# MercurialSDR_MISC.net
KiCad netlist of a schematic drawn in Altium Designer
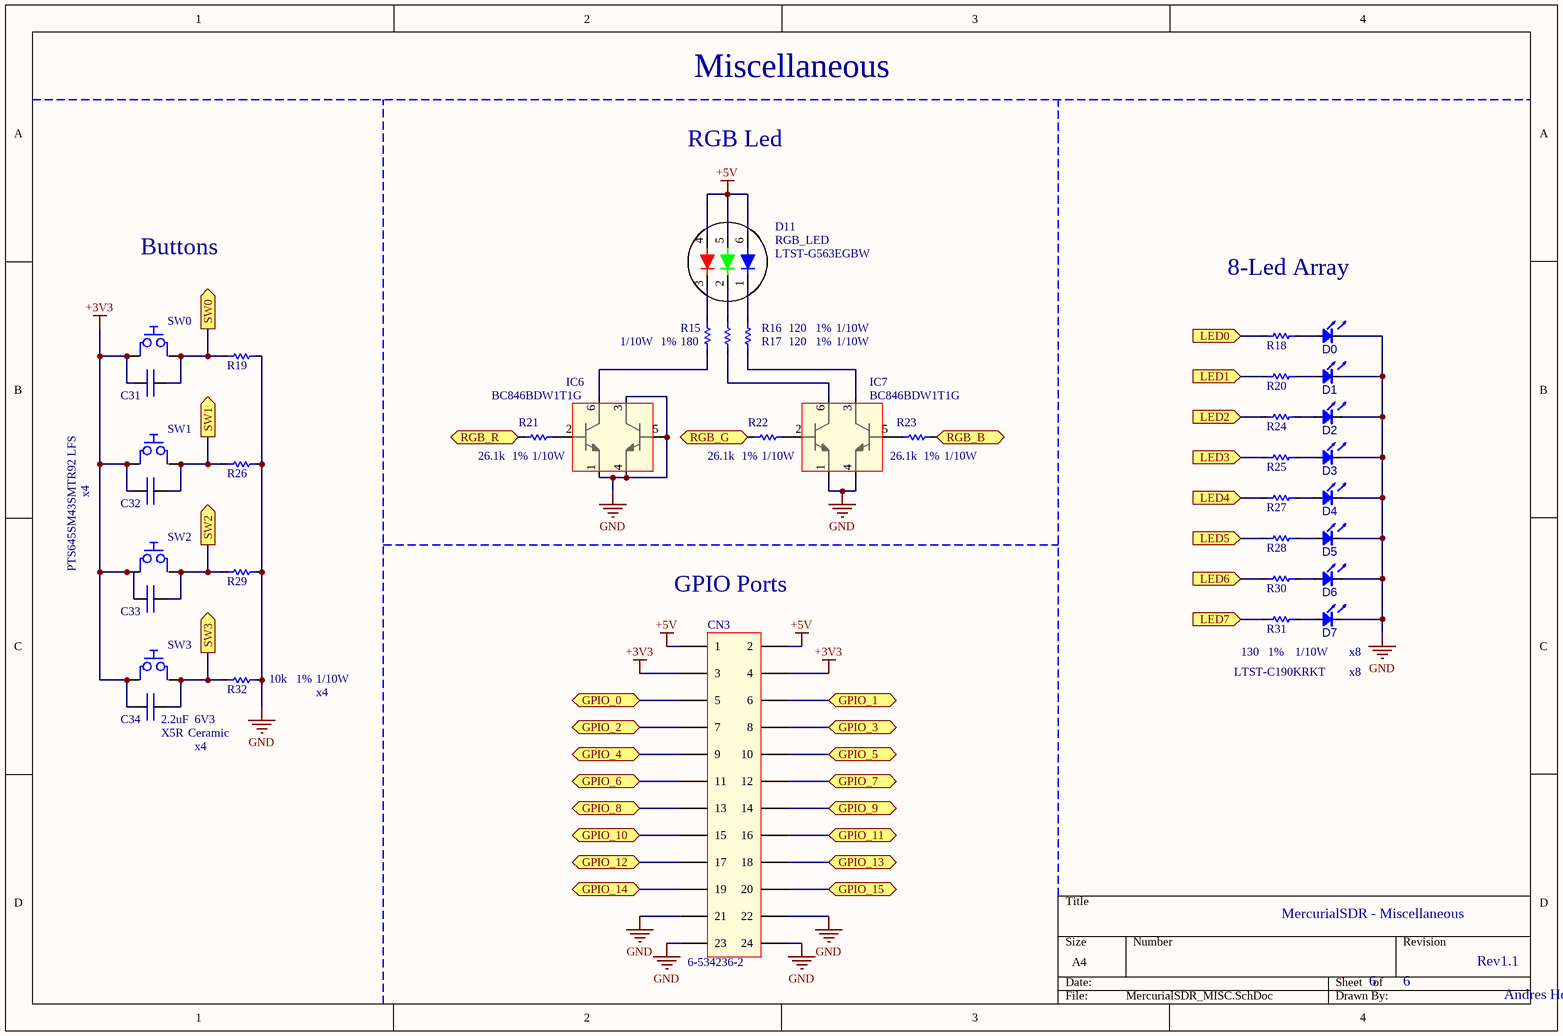
[diagram p0: MercurialSDR_MISC.SchDoc]

(export (version "E")
  (design (tool "Eeschema 10.0.6"))
  (components
    (comp (ref "C31")
      (value "Capacitor")
      (footprint "CAP_0603")
      (description "Capacitor no polarizado")
      (fields (field (name "PART NUMBER") "CL10A225KQ8NNNC"))
      (libsource (lib "MercurialSDR") (part "Cap"))
    )
    (comp (ref "C32")
      (value "Capacitor")
      (footprint "CAP_0603")
      (description "Capacitor no polarizado")
      (fields (field (name "PART NUMBER") "CL10A225KQ8NNNC"))
      (libsource (lib "MercurialSDR") (part "Cap"))
    )
    (comp (ref "C33")
      (value "Capacitor")
      (footprint "CAP_0603")
      (description "Capacitor no polarizado")
      (fields (field (name "PART NUMBER") "CL10A225KQ8NNNC"))
      (libsource (lib "MercurialSDR") (part "Cap"))
    )
    (comp (ref "C34")
      (value "2.2uF")
      (footprint "CAP_0603")
      (description "Capacitor no polarizado")
      (fields
        (field (name "TEMP COEF") "X5R")
        (field (name "PART NUMBER") "CL10A225KQ8NNNC")
        (field (name "VR") "6V3")
        (field (name "MATERIAL") "Ceramic")
        (field (name "Comment") "Capacitor")
      )
      (libsource (lib "MercurialSDR") (part "Cap"))
    )
    (comp (ref "CN3")
      (value "Connector")
      (footprint "CON_12x2")
      (description "Conector genérico 12x2")
      (fields (field (name "PART NUMBER") "6-534236-2"))
      (libsource (lib "MercurialSDR") (part "CN_12x2"))
    )
    (comp (ref "D0")
      (value "Led_small")
      (footprint "LED_0603")
      (fields (field (name "PART NUMBER") "LTST-C190KRKT"))
      (libsource (lib "MercurialSDR") (part "Led_small"))
    )
    (comp (ref "D1")
      (value "Led_small")
      (footprint "LED_0603")
      (fields (field (name "PART NUMBER") "LTST-C190KRKT"))
      (libsource (lib "MercurialSDR") (part "Led_small"))
    )
    (comp (ref "D2")
      (value "Led_small")
      (footprint "LED_0603")
      (fields (field (name "PART NUMBER") "LTST-C190KRKT"))
      (libsource (lib "MercurialSDR") (part "Led_small"))
    )
    (comp (ref "D3")
      (value "Led_small")
      (footprint "LED_0603")
      (fields (field (name "PART NUMBER") "LTST-C190KRKT"))
      (libsource (lib "MercurialSDR") (part "Led_small"))
    )
    (comp (ref "D4")
      (value "Led_small")
      (footprint "LED_0603")
      (fields (field (name "PART NUMBER") "LTST-C190KRKT"))
      (libsource (lib "MercurialSDR") (part "Led_small"))
    )
    (comp (ref "D5")
      (value "Led_small")
      (footprint "LED_0603")
      (fields (field (name "PART NUMBER") "LTST-C190KRKT"))
      (libsource (lib "MercurialSDR") (part "Led_small"))
    )
    (comp (ref "D6")
      (value "Led_small")
      (footprint "LED_0603")
      (fields (field (name "PART NUMBER") "LTST-C190KRKT"))
      (libsource (lib "MercurialSDR") (part "Led_small"))
    )
    (comp (ref "D7")
      (value "Led_small")
      (footprint "LED_0603")
      (fields (field (name "PART NUMBER") "LTST-C190KRKT"))
      (libsource (lib "MercurialSDR") (part "Led_small"))
    )
    (comp (ref "D11")
      (value "RGB_LED")
      (footprint "LED_RGB 5x5mm")
      (description "Led RGB")
      (fields (field (name "PART NUMBER") "LTST-G563EGBW"))
      (libsource (lib "MercurialSDR") (part "LED_RGB"))
    )
    (comp (ref "IC6")
      (value "BC846")
      (footprint "TSSOP-6")
      (description "TBJ NPN Dual")
      (fields (field (name "PART NUMBER") "BC846BDW1T1G"))
      (libsource (lib "MercurialSDR") (part "BC846BDW_1"))
    )
    (comp (ref "IC7")
      (value "BC846")
      (footprint "TSSOP-6")
      (description "TBJ NPN Dual")
      (fields (field (name "PART NUMBER") "BC846BDW1T1G"))
      (libsource (lib "MercurialSDR") (part "BC846BDW_1"))
    )
    (comp (ref "R15")
      (value "180")
      (footprint "RES_0603")
      (description "Resistor")
      (fields
        (field (name "POWER") "1/10W")
        (field (name "PART NUMBER") "CR0603-FX-1800ELF")
        (field (name "TOLERANCE") "1%")
        (field (name "Comment") "Resistor SMD")
      )
      (libsource (lib "MercurialSDR") (part "Res"))
    )
    (comp (ref "R16")
      (value "120")
      (footprint "RES_0603")
      (description "Resistor")
      (fields
        (field (name "POWER") "1/10W")
        (field (name "PART NUMBER") "CR0603-FX-1200ELF")
        (field (name "TOLERANCE") "1%")
        (field (name "Comment") "Resistor SMD")
      )
      (libsource (lib "MercurialSDR") (part "Res"))
    )
    (comp (ref "R17")
      (value "120")
      (footprint "RES_0603")
      (description "Resistor")
      (fields
        (field (name "POWER") "1/10W")
        (field (name "PART NUMBER") "CR0603-FX-1200ELF")
        (field (name "TOLERANCE") "1%")
        (field (name "Comment") "Resistor SMD")
      )
      (libsource (lib "MercurialSDR") (part "Res"))
    )
    (comp (ref "R18")
      (value "Resistor SMD")
      (footprint "RES_0603")
      (description "Resistor")
      (fields (field (name "POWER") "1/10W") (field (name "PART NUMBER") "CR0603-FX-1300ELF"))
      (libsource (lib "MercurialSDR") (part "Res"))
    )
    (comp (ref "R19")
      (value "10k")
      (footprint "RES_0603")
      (description "Resistor")
      (fields
        (field (name "POWER") "1/10W")
        (field (name "PART NUMBER") "CR0603-FX-1002EAS")
        (field (name "TOLERANCE") "1%")
        (field (name "Comment") "Resistor SMD")
      )
      (libsource (lib "MercurialSDR") (part "Res"))
    )
    (comp (ref "R20")
      (value "Resistor SMD")
      (footprint "RES_0603")
      (description "Resistor")
      (fields (field (name "POWER") "1/10W") (field (name "PART NUMBER") "CR0603-FX-1300ELF"))
      (libsource (lib "MercurialSDR") (part "Res"))
    )
    (comp (ref "R21")
      (value "26.1k")
      (footprint "RES_0603")
      (description "Resistor")
      (fields
        (field (name "POWER") "1/10W")
        (field (name "PART NUMBER") "CR0603-FX-2612ELF")
        (field (name "TOLERANCE") "1%")
        (field (name "Comment") "Resistor SMD")
      )
      (libsource (lib "MercurialSDR") (part "Res"))
    )
    (comp (ref "R22")
      (value "26.1k")
      (footprint "RES_0603")
      (description "Resistor")
      (fields
        (field (name "POWER") "1/10W")
        (field (name "PART NUMBER") "CR0603-FX-2612ELF")
        (field (name "TOLERANCE") "1%")
        (field (name "Comment") "Resistor SMD")
      )
      (libsource (lib "MercurialSDR") (part "Res"))
    )
    (comp (ref "R23")
      (value "26.1k")
      (footprint "RES_0603")
      (description "Resistor")
      (fields
        (field (name "POWER") "1/10W")
        (field (name "PART NUMBER") "CR0603-FX-2612ELF")
        (field (name "TOLERANCE") "1%")
        (field (name "Comment") "Resistor SMD")
      )
      (libsource (lib "MercurialSDR") (part "Res"))
    )
    (comp (ref "R24")
      (value "Resistor SMD")
      (footprint "RES_0603")
      (description "Resistor")
      (fields (field (name "POWER") "1/10W") (field (name "PART NUMBER") "CR0603-FX-1300ELF"))
      (libsource (lib "MercurialSDR") (part "Res"))
    )
    (comp (ref "R25")
      (value "Resistor SMD")
      (footprint "RES_0603")
      (description "Resistor")
      (fields (field (name "POWER") "1/10W") (field (name "PART NUMBER") "CR0603-FX-1300ELF"))
      (libsource (lib "MercurialSDR") (part "Res"))
    )
    (comp (ref "R26")
      (value "Resistor SMD")
      (footprint "RES_0603")
      (description "Resistor")
      (fields (field (name "POWER") "1/10W") (field (name "PART NUMBER") "CR0603-FX-1002EAS"))
      (libsource (lib "MercurialSDR") (part "Res"))
    )
    (comp (ref "R27")
      (value "Resistor SMD")
      (footprint "RES_0603")
      (description "Resistor")
      (fields (field (name "POWER") "1/10W") (field (name "PART NUMBER") "CR0603-FX-1300ELF"))
      (libsource (lib "MercurialSDR") (part "Res"))
    )
    (comp (ref "R28")
      (value "Resistor SMD")
      (footprint "RES_0603")
      (description "Resistor")
      (fields (field (name "POWER") "1/10W") (field (name "PART NUMBER") "CR0603-FX-1300ELF"))
      (libsource (lib "MercurialSDR") (part "Res"))
    )
    (comp (ref "R29")
      (value "Resistor SMD")
      (footprint "RES_0603")
      (description "Resistor")
      (fields (field (name "POWER") "1/10W") (field (name "PART NUMBER") "CR0603-FX-1002EAS"))
      (libsource (lib "MercurialSDR") (part "Res"))
    )
    (comp (ref "R30")
      (value "Resistor SMD")
      (footprint "RES_0603")
      (description "Resistor")
      (fields (field (name "POWER") "1/10W") (field (name "PART NUMBER") "CR0603-FX-1300ELF"))
      (libsource (lib "MercurialSDR") (part "Res"))
    )
    (comp (ref "R31")
      (value "130")
      (footprint "RES_0603")
      (description "Resistor")
      (fields
        (field (name "POWER") "1/10W")
        (field (name "PART NUMBER") "CR0603-FX-1300ELF")
        (field (name "TOLERANCE") "1%")
        (field (name "Comment") "Resistor SMD")
      )
      (libsource (lib "MercurialSDR") (part "Res"))
    )
    (comp (ref "R32")
      (value "Resistor SMD")
      (footprint "RES_0603")
      (description "Resistor")
      (fields (field (name "POWER") "1/10W") (field (name "PART NUMBER") "CR0603-FX-1002EAS"))
      (libsource (lib "MercurialSDR") (part "Res"))
    )
    (comp (ref "SW0")
      (value "Pulsador")
      (footprint "SWITCH_6X6mm")
      (fields (field (name "PART NUMBER") "PTS645SM43SMTR92 LFS"))
      (libsource (lib "MercurialSDR") (part "Pulsador"))
    )
    (comp (ref "SW1")
      (value "Pulsador")
      (footprint "SWITCH_6X6mm")
      (fields (field (name "PART NUMBER") "PTS645SM43SMTR92 LFS"))
      (libsource (lib "MercurialSDR") (part "Pulsador"))
    )
    (comp (ref "SW2")
      (value "Pulsador")
      (footprint "SWITCH_6X6mm")
      (fields (field (name "PART NUMBER") "PTS645SM43SMTR92 LFS"))
      (libsource (lib "MercurialSDR") (part "Pulsador"))
    )
    (comp (ref "SW3")
      (value "Pulsador")
      (footprint "SWITCH_6X6mm")
      (fields (field (name "PART NUMBER") "PTS645SM43SMTR92 LFS"))
      (libsource (lib "MercurialSDR") (part "Pulsador"))
    )
  )
  (nets
    (net (code "1") (name "+3V3") (class "Default")
      (node (ref "C31") (pin "1") (pinfunction "1_1") (pintype "passive"))
      (node (ref "C32") (pin "1") (pinfunction "1_1") (pintype "passive"))
      (node (ref "C33") (pin "1") (pinfunction "1_1") (pintype "passive"))
      (node (ref "C34") (pin "1") (pinfunction "1_1") (pintype "passive"))
      (node (ref "CN3") (pin "3") (pinfunction "3_3") (pintype "passive"))
      (node (ref "CN3") (pin "4") (pinfunction "4_4") (pintype "passive"))
      (node (ref "SW0") (pin "1") (pinfunction "1_1") (pintype "passive"))
      (node (ref "SW1") (pin "1") (pinfunction "1_1") (pintype "passive"))
      (node (ref "SW2") (pin "1") (pinfunction "1_1") (pintype "passive"))
      (node (ref "SW3") (pin "1") (pinfunction "1_1") (pintype "passive"))
    )
    (net (code "2") (name "+5V") (class "Default")
      (node (ref "CN3") (pin "1") (pinfunction "1_1") (pintype "passive"))
      (node (ref "CN3") (pin "2") (pinfunction "2_2") (pintype "passive"))
      (node (ref "D11") (pin "4") (pinfunction "RA_4") (pintype "passive"))
      (node (ref "D11") (pin "5") (pinfunction "GA_5") (pintype "passive"))
      (node (ref "D11") (pin "6") (pinfunction "BA_6") (pintype "passive"))
    )
    (net (code "3") (name "/GPIO_0") (class "Default")
      (node (ref "CN3") (pin "5") (pinfunction "5_5") (pintype "passive"))
    )
    (net (code "4") (name "/GPIO_1") (class "Default")
      (node (ref "CN3") (pin "6") (pinfunction "6_6") (pintype "passive"))
    )
    (net (code "5") (name "/GPIO_2") (class "Default")
      (node (ref "CN3") (pin "7") (pinfunction "7_7") (pintype "passive"))
    )
    (net (code "6") (name "/GPIO_3") (class "Default")
      (node (ref "CN3") (pin "8") (pinfunction "8_8") (pintype "passive"))
    )
    (net (code "7") (name "/GPIO_4") (class "Default")
      (node (ref "CN3") (pin "9") (pinfunction "9_9") (pintype "passive"))
    )
    (net (code "8") (name "/GPIO_5") (class "Default")
      (node (ref "CN3") (pin "10") (pinfunction "10_10") (pintype "passive"))
    )
    (net (code "9") (name "/GPIO_6") (class "Default")
      (node (ref "CN3") (pin "11") (pinfunction "11_11") (pintype "passive"))
    )
    (net (code "10") (name "/GPIO_7") (class "Default")
      (node (ref "CN3") (pin "12") (pinfunction "12_12") (pintype "passive"))
    )
    (net (code "11") (name "/GPIO_8") (class "Default")
      (node (ref "CN3") (pin "13") (pinfunction "13_13") (pintype "passive"))
    )
    (net (code "12") (name "/GPIO_9") (class "Default")
      (node (ref "CN3") (pin "14") (pinfunction "14_14") (pintype "passive"))
    )
    (net (code "13") (name "/GPIO_10") (class "Default")
      (node (ref "CN3") (pin "15") (pinfunction "15_15") (pintype "passive"))
    )
    (net (code "14") (name "/GPIO_11") (class "Default")
      (node (ref "CN3") (pin "16") (pinfunction "16_16") (pintype "passive"))
    )
    (net (code "15") (name "/GPIO_12") (class "Default")
      (node (ref "CN3") (pin "17") (pinfunction "17_17") (pintype "passive"))
    )
    (net (code "16") (name "/GPIO_13") (class "Default")
      (node (ref "CN3") (pin "18") (pinfunction "18_18") (pintype "passive"))
    )
    (net (code "17") (name "/GPIO_14") (class "Default")
      (node (ref "CN3") (pin "19") (pinfunction "19_19") (pintype "passive"))
    )
    (net (code "18") (name "/GPIO_15") (class "Default")
      (node (ref "CN3") (pin "20") (pinfunction "20_20") (pintype "passive"))
    )
    (net (code "19") (name "/LED0") (class "Default")
      (node (ref "R18") (pin "2") (pinfunction "2_2") (pintype "passive"))
    )
    (net (code "20") (name "/LED1") (class "Default")
      (node (ref "R20") (pin "2") (pinfunction "2_2") (pintype "passive"))
    )
    (net (code "21") (name "/LED2") (class "Default")
      (node (ref "R24") (pin "2") (pinfunction "2_2") (pintype "passive"))
    )
    (net (code "22") (name "/LED3") (class "Default")
      (node (ref "R25") (pin "2") (pinfunction "2_2") (pintype "passive"))
    )
    (net (code "23") (name "/LED4") (class "Default")
      (node (ref "R27") (pin "2") (pinfunction "2_2") (pintype "passive"))
    )
    (net (code "24") (name "/LED5") (class "Default")
      (node (ref "R28") (pin "2") (pinfunction "2_2") (pintype "passive"))
    )
    (net (code "25") (name "/LED6") (class "Default")
      (node (ref "R30") (pin "2") (pinfunction "2_2") (pintype "passive"))
    )
    (net (code "26") (name "/LED7") (class "Default")
      (node (ref "R31") (pin "2") (pinfunction "2_2") (pintype "passive"))
    )
    (net (code "27") (name "/RGB_B") (class "Default")
      (node (ref "R23") (pin "1") (pinfunction "1_1") (pintype "passive"))
    )
    (net (code "28") (name "/RGB_G") (class "Default")
      (node (ref "R22") (pin "2") (pinfunction "2_2") (pintype "passive"))
    )
    (net (code "29") (name "/RGB_R") (class "Default")
      (node (ref "R21") (pin "2") (pinfunction "2_2") (pintype "passive"))
    )
    (net (code "30") (name "/SW0") (class "Default")
      (node (ref "C31") (pin "2") (pinfunction "2_2") (pintype "passive"))
      (node (ref "R19") (pin "2") (pinfunction "2_2") (pintype "passive"))
      (node (ref "SW0") (pin "4") (pinfunction "4_4") (pintype "passive"))
    )
    (net (code "31") (name "/SW1") (class "Default")
      (node (ref "C32") (pin "2") (pinfunction "2_2") (pintype "passive"))
      (node (ref "R26") (pin "2") (pinfunction "2_2") (pintype "passive"))
      (node (ref "SW1") (pin "4") (pinfunction "4_4") (pintype "passive"))
    )
    (net (code "32") (name "/SW2") (class "Default")
      (node (ref "C33") (pin "2") (pinfunction "2_2") (pintype "passive"))
      (node (ref "R29") (pin "2") (pinfunction "2_2") (pintype "passive"))
      (node (ref "SW2") (pin "4") (pinfunction "4_4") (pintype "passive"))
    )
    (net (code "33") (name "/SW3") (class "Default")
      (node (ref "C34") (pin "2") (pinfunction "2_2") (pintype "passive"))
      (node (ref "R32") (pin "2") (pinfunction "2_2") (pintype "passive"))
      (node (ref "SW3") (pin "4") (pinfunction "4_4") (pintype "passive"))
    )
    (net (code "34") (name "GND") (class "Default")
      (node (ref "CN3") (pin "21") (pinfunction "21_21") (pintype "passive"))
      (node (ref "CN3") (pin "22") (pinfunction "22_22") (pintype "passive"))
      (node (ref "CN3") (pin "23") (pinfunction "23_23") (pintype "passive"))
      (node (ref "CN3") (pin "24") (pinfunction "24_24") (pintype "passive"))
      (node (ref "D0") (pin "2") (pinfunction "K_2") (pintype "passive"))
      (node (ref "D1") (pin "2") (pinfunction "K_2") (pintype "passive"))
      (node (ref "D2") (pin "2") (pinfunction "K_2") (pintype "passive"))
      (node (ref "D3") (pin "2") (pinfunction "K_2") (pintype "passive"))
      (node (ref "D4") (pin "2") (pinfunction "K_2") (pintype "passive"))
      (node (ref "D5") (pin "2") (pinfunction "K_2") (pintype "passive"))
      (node (ref "D6") (pin "2") (pinfunction "K_2") (pintype "passive"))
      (node (ref "D7") (pin "2") (pinfunction "K_2") (pintype "passive"))
      (node (ref "IC6") (pin "1") (pinfunction "E_1_1") (pintype "passive"))
      (node (ref "IC6") (pin "3") (pinfunction "C_2_3") (pintype "passive"))
      (node (ref "IC6") (pin "4") (pinfunction "E_2_4") (pintype "passive"))
      (node (ref "IC6") (pin "5") (pinfunction "B_2_5") (pintype "passive"))
      (node (ref "IC7") (pin "1") (pinfunction "E_1_1") (pintype "passive"))
      (node (ref "IC7") (pin "4") (pinfunction "E_2_4") (pintype "passive"))
      (node (ref "R19") (pin "1") (pinfunction "1_1") (pintype "passive"))
      (node (ref "R26") (pin "1") (pinfunction "1_1") (pintype "passive"))
      (node (ref "R29") (pin "1") (pinfunction "1_1") (pintype "passive"))
      (node (ref "R32") (pin "1") (pinfunction "1_1") (pintype "passive"))
    )
    (net (code "35") (name "Net-(D0-A)") (class "Default")
      (node (ref "D0") (pin "1") (pinfunction "A_1") (pintype "passive"))
      (node (ref "R18") (pin "1") (pinfunction "1_1") (pintype "passive"))
    )
    (net (code "36") (name "Net-(D1-A)") (class "Default")
      (node (ref "D1") (pin "1") (pinfunction "A_1") (pintype "passive"))
      (node (ref "R20") (pin "1") (pinfunction "1_1") (pintype "passive"))
    )
    (net (code "37") (name "Net-(D2-A)") (class "Default")
      (node (ref "D2") (pin "1") (pinfunction "A_1") (pintype "passive"))
      (node (ref "R24") (pin "1") (pinfunction "1_1") (pintype "passive"))
    )
    (net (code "38") (name "Net-(D3-A)") (class "Default")
      (node (ref "D3") (pin "1") (pinfunction "A_1") (pintype "passive"))
      (node (ref "R25") (pin "1") (pinfunction "1_1") (pintype "passive"))
    )
    (net (code "39") (name "Net-(D4-A)") (class "Default")
      (node (ref "D4") (pin "1") (pinfunction "A_1") (pintype "passive"))
      (node (ref "R27") (pin "1") (pinfunction "1_1") (pintype "passive"))
    )
    (net (code "40") (name "Net-(D5-A)") (class "Default")
      (node (ref "D5") (pin "1") (pinfunction "A_1") (pintype "passive"))
      (node (ref "R28") (pin "1") (pinfunction "1_1") (pintype "passive"))
    )
    (net (code "41") (name "Net-(D6-A)") (class "Default")
      (node (ref "D6") (pin "1") (pinfunction "A_1") (pintype "passive"))
      (node (ref "R30") (pin "1") (pinfunction "1_1") (pintype "passive"))
    )
    (net (code "42") (name "Net-(D7-A)") (class "Default")
      (node (ref "D7") (pin "1") (pinfunction "A_1") (pintype "passive"))
      (node (ref "R31") (pin "1") (pinfunction "1_1") (pintype "passive"))
    )
    (net (code "43") (name "Net-(D11-BK)") (class "Default")
      (node (ref "D11") (pin "1") (pinfunction "BK_1") (pintype "passive"))
      (node (ref "R17") (pin "1") (pinfunction "1_1") (pintype "passive"))
    )
    (net (code "44") (name "Net-(D11-GK)") (class "Default")
      (node (ref "D11") (pin "2") (pinfunction "GK_2") (pintype "passive"))
      (node (ref "R16") (pin "1") (pinfunction "1_1") (pintype "passive"))
    )
    (net (code "45") (name "Net-(D11-RK)") (class "Default")
      (node (ref "D11") (pin "3") (pinfunction "RK_3") (pintype "passive"))
      (node (ref "R15") (pin "1") (pinfunction "1_1") (pintype "passive"))
    )
    (net (code "46") (name "Net-(IC6-B_1)") (class "Default")
      (node (ref "IC6") (pin "2") (pinfunction "B_1_2") (pintype "passive"))
      (node (ref "R21") (pin "1") (pinfunction "1_1") (pintype "passive"))
    )
    (net (code "47") (name "Net-(IC6-C_1)") (class "Default")
      (node (ref "IC6") (pin "6") (pinfunction "C_1_6") (pintype "passive"))
      (node (ref "R15") (pin "2") (pinfunction "2_2") (pintype "passive"))
    )
    (net (code "48") (name "Net-(IC7-B_1)") (class "Default")
      (node (ref "IC7") (pin "2") (pinfunction "B_1_2") (pintype "passive"))
      (node (ref "R22") (pin "1") (pinfunction "1_1") (pintype "passive"))
    )
    (net (code "49") (name "Net-(IC7-B_2)") (class "Default")
      (node (ref "IC7") (pin "5") (pinfunction "B_2_5") (pintype "passive"))
      (node (ref "R23") (pin "2") (pinfunction "2_2") (pintype "passive"))
    )
    (net (code "50") (name "Net-(IC7-C_1)") (class "Default")
      (node (ref "IC7") (pin "6") (pinfunction "C_1_6") (pintype "passive"))
      (node (ref "R16") (pin "2") (pinfunction "2_2") (pintype "passive"))
    )
    (net (code "51") (name "Net-(IC7-C_2)") (class "Default")
      (node (ref "IC7") (pin "3") (pinfunction "C_2_3") (pintype "passive"))
      (node (ref "R17") (pin "2") (pinfunction "2_2") (pintype "passive"))
    )
    (net (code "52") (name "unconnected-(SW0-Pad2)") (class "Default")
      (node (ref "SW0") (pin "2") (pinfunction "2_2") (pintype "passive"))
    )
    (net (code "53") (name "unconnected-(SW0-Pad3)") (class "Default")
      (node (ref "SW0") (pin "3") (pinfunction "3_3") (pintype "passive"))
    )
    (net (code "54") (name "unconnected-(SW1-Pad2)") (class "Default")
      (node (ref "SW1") (pin "2") (pinfunction "2_2") (pintype "passive"))
    )
    (net (code "55") (name "unconnected-(SW1-Pad3)") (class "Default")
      (node (ref "SW1") (pin "3") (pinfunction "3_3") (pintype "passive"))
    )
    (net (code "56") (name "unconnected-(SW2-Pad2)") (class "Default")
      (node (ref "SW2") (pin "2") (pinfunction "2_2") (pintype "passive"))
    )
    (net (code "57") (name "unconnected-(SW2-Pad3)") (class "Default")
      (node (ref "SW2") (pin "3") (pinfunction "3_3") (pintype "passive"))
    )
    (net (code "58") (name "unconnected-(SW3-Pad2)") (class "Default")
      (node (ref "SW3") (pin "2") (pinfunction "2_2") (pintype "passive"))
    )
    (net (code "59") (name "unconnected-(SW3-Pad3)") (class "Default")
      (node (ref "SW3") (pin "3") (pinfunction "3_3") (pintype "passive"))
    )
  )
)
